# PR9016.net
KiCad netlist of a schematic drawn in EAGLE
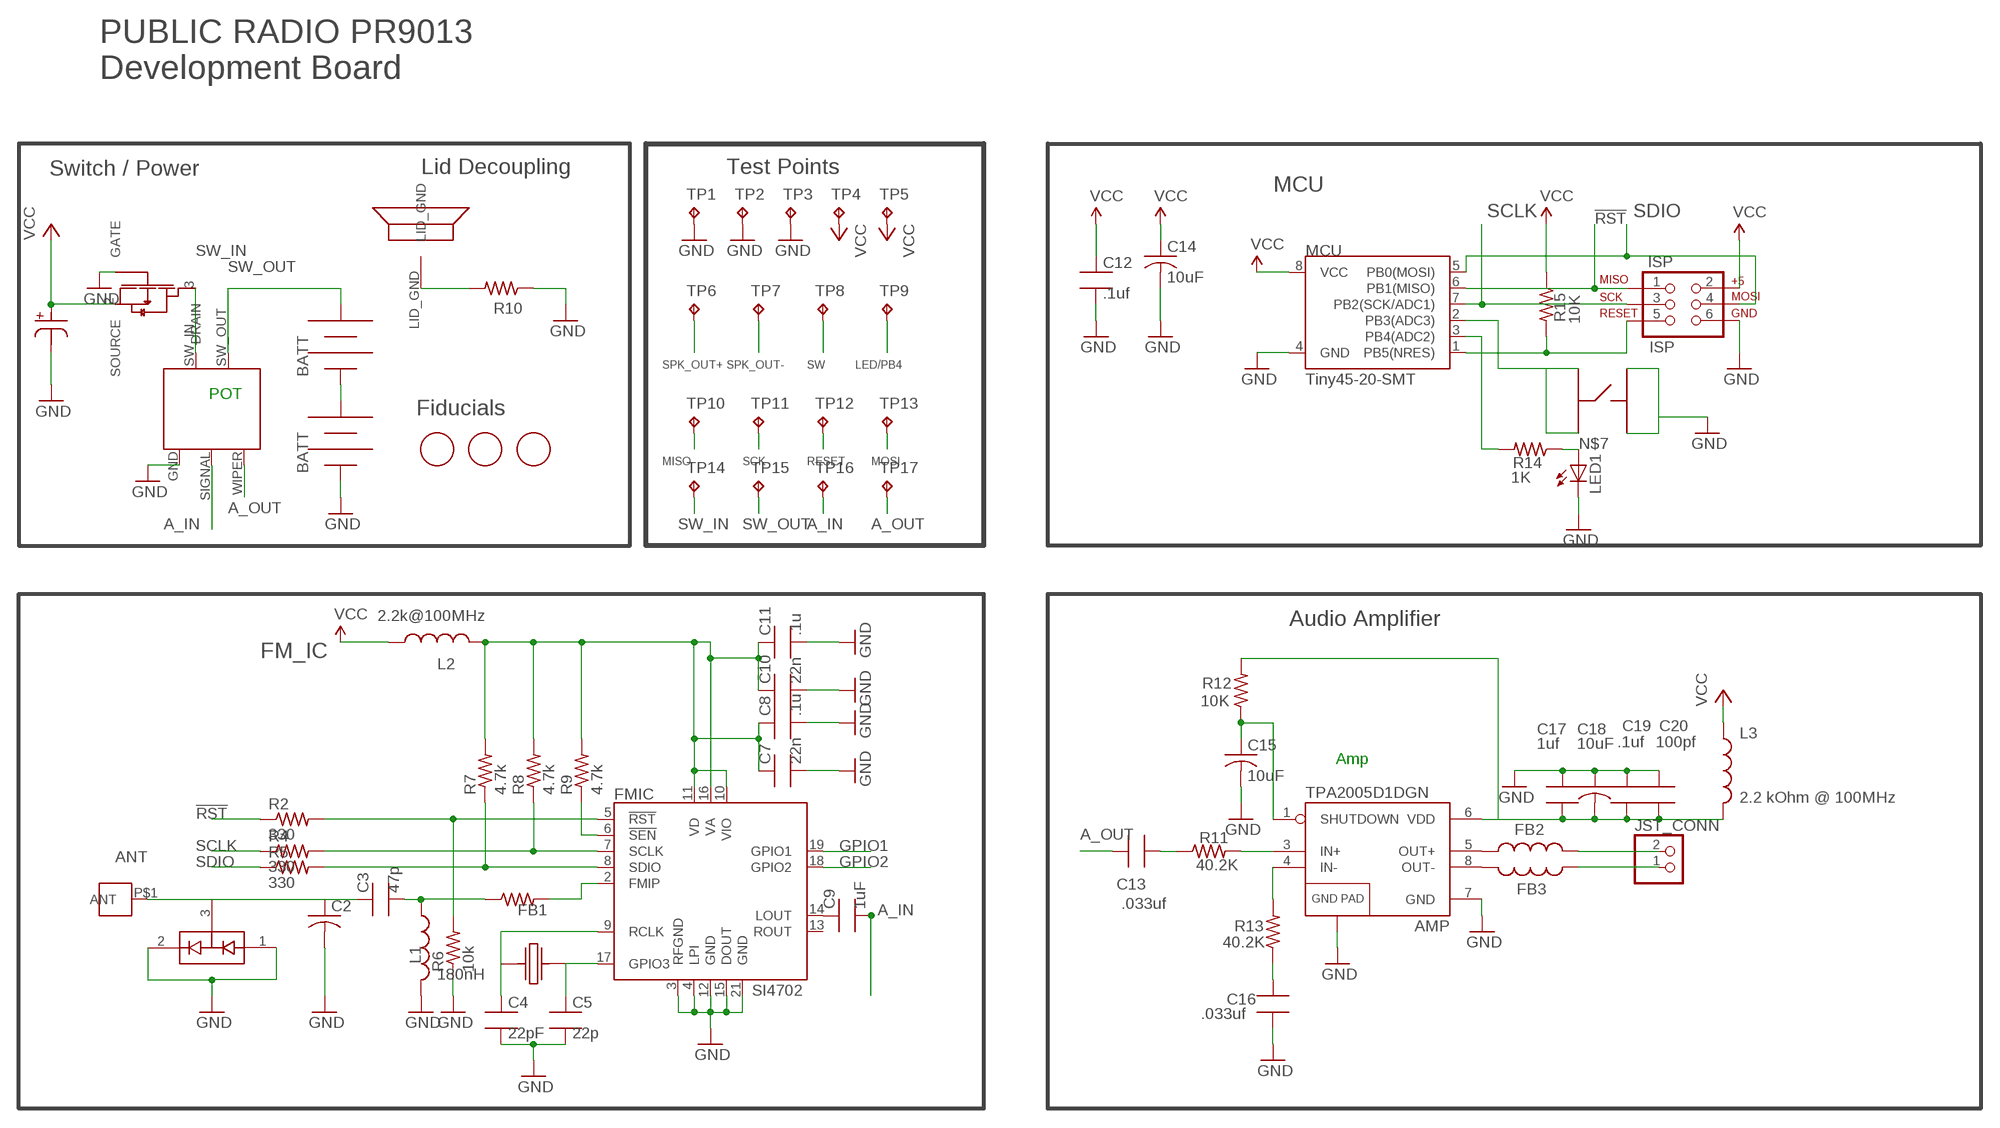
[diagram p0: schematic, sheet 1]

(export (version "E")
  (design (tool "Eeschema 10.0.6"))
  (components
    (comp (ref "AMP")
      (value "TPA2005D1DGN")
      (footprint "eagle-import:POWER-SOP8")
      (libsource (lib "eagle-import") (part "TPA2005D1DGN"))
    )
    (comp (ref "ANT_MOUNT")
      (value "M3_SCREW_POST")
      (footprint "eagle-import:M3_SCREW_POST")
      (libsource (lib "eagle-import") (part "M3_SCREW_POST"))
    )
    (comp (ref "C1")
      (value "220uF")
      (footprint "eagle-import:NICHICON_SERIESUD")
      (libsource (lib "eagle-import") (part "NICHICON_SERIESUD"))
    )
    (comp (ref "C2")
      (value "C-USC0805")
      (footprint "eagle-import:C0805")
      (libsource (lib "eagle-import") (part "C-USC0805"))
    )
    (comp (ref "C3")
      (value "47p")
      (footprint "eagle-import:C0402_WORTHINGTON")
      (libsource (lib "eagle-import") (part "CAP_SMT"))
    )
    (comp (ref "C4")
      (value "22pF")
      (footprint "eagle-import:C0402_WORTHINGTON")
      (libsource (lib "eagle-import") (part "CAP_SMT"))
    )
    (comp (ref "C5")
      (value "22p")
      (footprint "eagle-import:C0402_WORTHINGTON")
      (libsource (lib "eagle-import") (part "CAP_SMT"))
    )
    (comp (ref "C7")
      (value "22n")
      (footprint "eagle-import:C0402_WORTHINGTON")
      (libsource (lib "eagle-import") (part "CAP_SMT"))
    )
    (comp (ref "C8")
      (value ".1u")
      (footprint "eagle-import:C0402_WORTHINGTON")
      (libsource (lib "eagle-import") (part "CAP_SMT"))
    )
    (comp (ref "C9")
      (value "1uF")
      (footprint "eagle-import:C0402_WORTHINGTON")
      (libsource (lib "eagle-import") (part "CAP_SMT"))
    )
    (comp (ref "C10")
      (value "22n")
      (footprint "eagle-import:C0402_WORTHINGTON")
      (libsource (lib "eagle-import") (part "CAP_SMT"))
    )
    (comp (ref "C11")
      (value ".1u")
      (footprint "eagle-import:C0402_WORTHINGTON")
      (libsource (lib "eagle-import") (part "CAP_SMT"))
    )
    (comp (ref "C12")
      (value ".1uf")
      (footprint "eagle-import:C0402_WORTHINGTON")
      (libsource (lib "eagle-import") (part "CAP_SMT"))
    )
    (comp (ref "C13")
      (value ".033uf")
      (footprint "eagle-import:C0402_WORTHINGTON")
      (libsource (lib "eagle-import") (part "CAP_SMT"))
    )
    (comp (ref "C14")
      (value "10uF")
      (footprint "eagle-import:C0603")
      (libsource (lib "eagle-import") (part "C-USC0603"))
    )
    (comp (ref "C15")
      (value "10uF")
      (footprint "eagle-import:C0603")
      (libsource (lib "eagle-import") (part "C-USC0603"))
    )
    (comp (ref "C16")
      (value ".033uf")
      (footprint "eagle-import:C0402_WORTHINGTON")
      (libsource (lib "eagle-import") (part "CAP_SMT"))
    )
    (comp (ref "C17")
      (value "1uf")
      (footprint "eagle-import:C0402_WORTHINGTON")
      (libsource (lib "eagle-import") (part "CAP_SMT"))
    )
    (comp (ref "C18")
      (value "10uF")
      (footprint "eagle-import:C0603")
      (libsource (lib "eagle-import") (part "C-USC0603"))
    )
    (comp (ref "C19")
      (value ".1uf")
      (footprint "eagle-import:C0402_WORTHINGTON")
      (libsource (lib "eagle-import") (part "CAP_SMT"))
    )
    (comp (ref "C20")
      (value "100pf")
      (footprint "eagle-import:C0402_WORTHINGTON")
      (libsource (lib "eagle-import") (part "CAP_SMT"))
    )
    (comp (ref "D1")
      (value "BAV99")
      (footprint "eagle-import:SOT23")
      (libsource (lib "eagle-import") (part "BAV99"))
    )
    (comp (ref "FB1")
      (value "R-US_R0402")
      (footprint "eagle-import:R0402")
      (libsource (lib "eagle-import") (part "R-US_R0402"))
    )
    (comp (ref "FB2")
      (value "INDUCTOR0805")
      (footprint "eagle-import:0805")
      (libsource (lib "eagle-import") (part "INDUCTOR0805"))
    )
    (comp (ref "FB3")
      (value "INDUCTOR0805")
      (footprint "eagle-import:0805")
      (libsource (lib "eagle-import") (part "INDUCTOR0805"))
    )
    (comp (ref "FET1")
      (value "AO3435")
      (footprint "eagle-import:AO3435")
      (libsource (lib "eagle-import") (part "AO3435"))
    )
    (comp (ref "FMIC")
      (value "SI4702")
      (footprint "eagle-import:SI470X")
      (libsource (lib "eagle-import") (part "SI470X"))
    )
    (comp (ref "ISP")
      (value "ISP")
      (footprint "eagle-import:2X3-NS")
      (libsource (lib "eagle-import") (part "AVR_SPI_PRG_6NS"))
    )
    (comp (ref "JP5")
      (value "BK-92_MPD_AA_BATT_CLIP")
      (footprint "eagle-import:BK-92_MPD_AA_BATT_CLIP")
      (libsource (lib "eagle-import") (part "BK-92_MPD_AA_BATT_CLIP"))
    )
    (comp (ref "JP6")
      (value "BK-92_MPD_AA_BATT_CLIP")
      (footprint "eagle-import:BK-92_MPD_AA_BATT_CLIP")
      (libsource (lib "eagle-import") (part "BK-92_MPD_AA_BATT_CLIP"))
    )
    (comp (ref "JST_CONN")
      (value "JST_2PIN-SMT-RA")
      (footprint "eagle-import:JST-PH-2-SMT-RA")
      (libsource (lib "eagle-import") (part "JST_2PIN-SMT-RA"))
    )
    (comp (ref "L1")
      (value "180nH")
      (footprint "eagle-import:0805")
      (libsource (lib "eagle-import") (part "INDUCTOR0805"))
    )
    (comp (ref "L2")
      (value "2.2k@100MHz")
      (footprint "eagle-import:C0402_WORTHINGTON")
      (libsource (lib "eagle-import") (part "INDUCTOR"))
    )
    (comp (ref "L3")
      (value "2.2 kOhm @ 100MHz")
      (footprint "eagle-import:C0402_WORTHINGTON")
      (libsource (lib "eagle-import") (part "INDUCTOR"))
    )
    (comp (ref "LED1")
      (value "LEDSML0603")
      (footprint "eagle-import:SML0603")
      (libsource (lib "eagle-import") (part "LEDSML0603"))
    )
    (comp (ref "MARK1")
      (value "FIDUCIAL")
      (footprint "eagle-import:FIDUCIAL_1MM")
      (libsource (lib "eagle-import") (part "FIDUCIAL"))
    )
    (comp (ref "MARK2")
      (value "FIDUCIAL")
      (footprint "eagle-import:FIDUCIAL_1MM")
      (libsource (lib "eagle-import") (part "FIDUCIAL"))
    )
    (comp (ref "MARK3")
      (value "FIDUCIAL")
      (footprint "eagle-import:FIDUCIAL_1MM")
      (libsource (lib "eagle-import") (part "FIDUCIAL"))
    )
    (comp (ref "MCU")
      (value "Tiny45-20-SMT")
      (footprint "eagle-import:SO08-EIAJ")
      (libsource (lib "eagle-import") (part "ATTINY45TINY85-20-SMT"))
    )
    (comp (ref "R1")
      (value "RV170SF_TAIWANA_POT_SW")
      (footprint "eagle-import:RV170SF_TAIWANA_POT_SW")
      (libsource (lib "eagle-import") (part "RV170SF_TAIWANA_POT_SW"))
    )
    (comp (ref "R2")
      (value "330")
      (footprint "eagle-import:C0402_WORTHINGTON")
      (libsource (lib "eagle-import") (part "RES_SMT"))
    )
    (comp (ref "R4")
      (value "330")
      (footprint "eagle-import:C0402_WORTHINGTON")
      (libsource (lib "eagle-import") (part "RES_SMT"))
    )
    (comp (ref "R5")
      (value "330")
      (footprint "eagle-import:C0402_WORTHINGTON")
      (libsource (lib "eagle-import") (part "RES_SMT"))
    )
    (comp (ref "R6")
      (value "10k")
      (footprint "eagle-import:R0402")
      (libsource (lib "eagle-import") (part "R-US_R0402"))
    )
    (comp (ref "R7")
      (value "4.7k")
      (footprint "eagle-import:C0402_WORTHINGTON")
      (libsource (lib "eagle-import") (part "RES_SMT"))
    )
    (comp (ref "R8")
      (value "4.7k")
      (footprint "eagle-import:C0402_WORTHINGTON")
      (libsource (lib "eagle-import") (part "RES_SMT"))
    )
    (comp (ref "R9")
      (value "4.7k")
      (footprint "eagle-import:C0402_WORTHINGTON")
      (libsource (lib "eagle-import") (part "RES_SMT"))
    )
    (comp (ref "R10")
      (value "R-US_R0805")
      (footprint "eagle-import:R0805")
      (libsource (lib "eagle-import") (part "R-US_R0805"))
    )
    (comp (ref "R11")
      (value "40.2K")
      (footprint "eagle-import:C0402_WORTHINGTON")
      (libsource (lib "eagle-import") (part "RES_SMT"))
    )
    (comp (ref "R12")
      (value "10K")
      (footprint "eagle-import:C0402_WORTHINGTON")
      (libsource (lib "eagle-import") (part "RES_SMT"))
    )
    (comp (ref "R13")
      (value "40.2K")
      (footprint "eagle-import:C0402_WORTHINGTON")
      (libsource (lib "eagle-import") (part "RES_SMT"))
    )
    (comp (ref "R14")
      (value "1K")
      (footprint "eagle-import:C0402_WORTHINGTON")
      (libsource (lib "eagle-import") (part "RES_SMT"))
    )
    (comp (ref "R15")
      (value "10K")
      (footprint "eagle-import:C0402_WORTHINGTON")
      (libsource (lib "eagle-import") (part "RES_SMT"))
    )
    (comp (ref "SPKR_PLACE")
      (value "CE32A_FOR_JST")
      (footprint "eagle-import:CE32A_FOR_JST")
      (libsource (lib "eagle-import") (part "PR_Parts_Library_CE32A_FOR_JST"))
    )
    (comp (ref "SW1")
      (value "C&K_PTS645")
      (footprint "eagle-import:C&K_TACTILE_SWITCH")
      (libsource (lib "eagle-import") (part "C&K_PTS645"))
    )
    (comp (ref "TP1")
      (value "TPTP20R")
      (footprint "eagle-import:TP20R")
      (libsource (lib "eagle-import") (part "TPTP20R"))
    )
    (comp (ref "TP2")
      (value "TPTP20R")
      (footprint "eagle-import:TP20R")
      (libsource (lib "eagle-import") (part "TPTP20R"))
    )
    (comp (ref "TP3")
      (value "TPTP20R")
      (footprint "eagle-import:TP20R")
      (libsource (lib "eagle-import") (part "TPTP20R"))
    )
    (comp (ref "TP4")
      (value "TPTP20R")
      (footprint "eagle-import:TP20R")
      (libsource (lib "eagle-import") (part "TPTP20R"))
    )
    (comp (ref "TP5")
      (value "TPTP20R")
      (footprint "eagle-import:TP20R")
      (libsource (lib "eagle-import") (part "TPTP20R"))
    )
    (comp (ref "TP6")
      (value "TPTP20R")
      (footprint "eagle-import:TP20R")
      (libsource (lib "eagle-import") (part "TPTP20R"))
    )
    (comp (ref "TP7")
      (value "TPTP20R")
      (footprint "eagle-import:TP20R")
      (libsource (lib "eagle-import") (part "TPTP20R"))
    )
    (comp (ref "TP8")
      (value "TPTP20R")
      (footprint "eagle-import:TP20R")
      (libsource (lib "eagle-import") (part "TPTP20R"))
    )
    (comp (ref "TP9")
      (value "TPTP20R")
      (footprint "eagle-import:TP20R")
      (libsource (lib "eagle-import") (part "TPTP20R"))
    )
    (comp (ref "TP10")
      (value "TPTP20R")
      (footprint "eagle-import:TP20R")
      (libsource (lib "eagle-import") (part "TPTP20R"))
    )
    (comp (ref "TP11")
      (value "TPTP20R")
      (footprint "eagle-import:TP20R")
      (libsource (lib "eagle-import") (part "TPTP20R"))
    )
    (comp (ref "TP12")
      (value "TPTP20R")
      (footprint "eagle-import:TP20R")
      (libsource (lib "eagle-import") (part "TPTP20R"))
    )
    (comp (ref "TP13")
      (value "TPTP20R")
      (footprint "eagle-import:TP20R")
      (libsource (lib "eagle-import") (part "TPTP20R"))
    )
    (comp (ref "TP14")
      (value "TPTP20R")
      (footprint "eagle-import:TP20R")
      (libsource (lib "eagle-import") (part "TPTP20R"))
    )
    (comp (ref "TP15")
      (value "TPTP20R")
      (footprint "eagle-import:TP20R")
      (libsource (lib "eagle-import") (part "TPTP20R"))
    )
    (comp (ref "TP16")
      (value "TPTP20R")
      (footprint "eagle-import:TP20R")
      (libsource (lib "eagle-import") (part "TPTP20R"))
    )
    (comp (ref "TP17")
      (value "TPTP20R")
      (footprint "eagle-import:TP20R")
      (libsource (lib "eagle-import") (part "TPTP20R"))
    )
    (comp (ref "Y1")
      (value "ABS25XTAL")
      (footprint "eagle-import:ABS25XTAL")
      (libsource (lib "eagle-import") (part "ABS25XTAL"))
    )
  )
  (nets
    (net (code "1") (name "/ANT") (class "Default")
      (node (ref "ANT_MOUNT") (pin "P$1") (pinfunction "ANT_P$1") (pintype "bidirectional"))
      (node (ref "C2") (pin "1") (pinfunction "1_1") (pintype "passive"))
      (node (ref "C3") (pin "1") (pinfunction "1_1") (pintype "passive"))
      (node (ref "D1") (pin "3") (pinfunction "COM_3") (pintype "bidirectional"))
    )
    (net (code "2") (name "/A_IN") (class "Default")
      (node (ref "C9") (pin "2") (pinfunction "2_2") (pintype "passive"))
      (node (ref "R1") (pin "SIGNAL") (pinfunction "SIGNAL_SIGNAL") (pintype "bidirectional"))
      (node (ref "TP16") (pin "TP") (pinfunction "TP_TP") (pintype "input"))
    )
    (net (code "3") (name "/A_OUT") (class "Default")
      (node (ref "C13") (pin "1") (pinfunction "1_1") (pintype "passive"))
      (node (ref "R1") (pin "WIPER") (pinfunction "WIPER_WIPER") (pintype "bidirectional"))
      (node (ref "TP17") (pin "TP") (pinfunction "TP_TP") (pintype "input"))
    )
    (net (code "4") (name "/GPIO1") (class "Default")
      (node (ref "FMIC") (pin "19") (pinfunction "GPIO1_19") (pintype "bidirectional"))
    )
    (net (code "5") (name "/GPIO2") (class "Default")
      (node (ref "FMIC") (pin "18") (pinfunction "GPIO2_18") (pintype "bidirectional"))
    )
    (net (code "6") (name "/LED{slash}PB4") (class "Default")
      (node (ref "MCU") (pin "3") (pinfunction "PB4(ADC2)_3") (pintype "bidirectional"))
      (node (ref "R14") (pin "2") (pinfunction "2_2") (pintype "passive"))
      (node (ref "TP9") (pin "TP") (pinfunction "TP_TP") (pintype "input"))
    )
    (net (code "7") (name "/N$7") (class "Default")
      (node (ref "LED1") (pin "A") (pinfunction "A_A") (pintype "passive"))
      (node (ref "R14") (pin "1") (pinfunction "1_1") (pintype "passive"))
    )
    (net (code "8") (name "/RESET") (class "Default")
      (node (ref "ISP") (pin "5") (pinfunction "5_5") (pintype "passive"))
      (node (ref "MCU") (pin "1") (pinfunction "PB5(NRES)_1") (pintype "bidirectional"))
      (node (ref "R15") (pin "2") (pinfunction "2_2") (pintype "passive"))
      (node (ref "TP12") (pin "TP") (pinfunction "TP_TP") (pintype "input"))
    )
    (net (code "9") (name "/SCLK") (class "Default")
      (node (ref "ISP") (pin "3") (pinfunction "3_3") (pintype "passive"))
      (node (ref "MCU") (pin "7") (pinfunction "PB2(SCK/ADC1)_7") (pintype "bidirectional"))
      (node (ref "R4") (pin "1") (pinfunction "1_1") (pintype "passive"))
      (node (ref "TP11") (pin "TP") (pinfunction "TP_TP") (pintype "input"))
    )
    (net (code "10") (name "/SDIO") (class "Default")
      (node (ref "ISP") (pin "4") (pinfunction "4_4") (pintype "passive"))
      (node (ref "MCU") (pin "5") (pinfunction "PB0(MOSI)_5") (pintype "bidirectional"))
      (node (ref "R5") (pin "1") (pinfunction "1_1") (pintype "passive"))
      (node (ref "TP13") (pin "TP") (pinfunction "TP_TP") (pintype "input"))
    )
    (net (code "11") (name "/SPK_OUT+") (class "Default")
      (node (ref "FB2") (pin "2") (pinfunction "2_2") (pintype "passive"))
      (node (ref "JST_CONN") (pin "2") (pinfunction "1_2") (pintype "passive"))
      (node (ref "TP6") (pin "TP") (pinfunction "TP_TP") (pintype "input"))
    )
    (net (code "12") (name "/SPK_OUT-") (class "Default")
      (node (ref "FB3") (pin "1") (pinfunction "1_1") (pintype "passive"))
      (node (ref "JST_CONN") (pin "1") (pinfunction "2_1") (pintype "passive"))
      (node (ref "TP7") (pin "TP") (pinfunction "TP_TP") (pintype "input"))
    )
    (net (code "13") (name "/SW") (class "Default")
      (node (ref "MCU") (pin "2") (pinfunction "PB3(ADC3)_2") (pintype "bidirectional"))
      (node (ref "SW1") (pin "P$3") (pinfunction "P$3_P$3") (pintype "bidirectional"))
      (node (ref "SW1") (pin "P$4") (pinfunction "P$4_P$4") (pintype "bidirectional"))
      (node (ref "TP8") (pin "TP") (pinfunction "TP_TP") (pintype "input"))
    )
    (net (code "14") (name "/SW_IN") (class "Default")
      (node (ref "FET1") (pin "3") (pinfunction "DRAIN_3") (pintype "bidirectional"))
      (node (ref "R1") (pin "SW_IN") (pinfunction "SW_IN_SW_IN") (pintype "bidirectional"))
      (node (ref "TP14") (pin "TP") (pinfunction "TP_TP") (pintype "input"))
    )
    (net (code "15") (name "/SW_OUT") (class "Default")
      (node (ref "JP5") (pin "POS") (pinfunction "POS_POS") (pintype "bidirectional"))
      (node (ref "JP5") (pin "POS@2") (pinfunction "POS_POS@2") (pintype "bidirectional"))
      (node (ref "R1") (pin "SW_OUT") (pinfunction "SW_OUT_SW_OUT") (pintype "bidirectional"))
      (node (ref "TP15") (pin "TP") (pinfunction "TP_TP") (pintype "input"))
    )
    (net (code "16") (name "/~{RST}") (class "Default")
      (node (ref "ISP") (pin "1") (pinfunction "1_1") (pintype "passive"))
      (node (ref "MCU") (pin "6") (pinfunction "PB1(MISO)_6") (pintype "bidirectional"))
      (node (ref "R2") (pin "1") (pinfunction "1_1") (pintype "passive"))
      (node (ref "TP10") (pin "TP") (pinfunction "TP_TP") (pintype "input"))
    )
    (net (code "17") (name "GND") (class "Default")
      (node (ref "AMP") (pin "7") (pinfunction "GND_7") (pintype "power_in"))
      (node (ref "AMP") (pin "9") (pinfunction "GND_9") (pintype "power_in"))
      (node (ref "C1") (pin "P$2") (pinfunction "P$2_P$2") (pintype "bidirectional"))
      (node (ref "C10") (pin "2") (pinfunction "2_2") (pintype "passive"))
      (node (ref "C11") (pin "2") (pinfunction "2_2") (pintype "passive"))
      (node (ref "C12") (pin "2") (pinfunction "2_2") (pintype "passive"))
      (node (ref "C14") (pin "2") (pinfunction "2_2") (pintype "passive"))
      (node (ref "C15") (pin "2") (pinfunction "2_2") (pintype "passive"))
      (node (ref "C16") (pin "1") (pinfunction "1_1") (pintype "passive"))
      (node (ref "C17") (pin "1") (pinfunction "1_1") (pintype "passive"))
      (node (ref "C18") (pin "1") (pinfunction "1_1") (pintype "passive"))
      (node (ref "C19") (pin "1") (pinfunction "1_1") (pintype "passive"))
      (node (ref "C2") (pin "2") (pinfunction "2_2") (pintype "passive"))
      (node (ref "C20") (pin "1") (pinfunction "1_1") (pintype "passive"))
      (node (ref "C4") (pin "2") (pinfunction "2_2") (pintype "passive"))
      (node (ref "C5") (pin "2") (pinfunction "2_2") (pintype "passive"))
      (node (ref "C7") (pin "2") (pinfunction "2_2") (pintype "passive"))
      (node (ref "C8") (pin "2") (pinfunction "2_2") (pintype "passive"))
      (node (ref "D1") (pin "1") (pinfunction "A1_1") (pintype "bidirectional"))
      (node (ref "D1") (pin "2") (pinfunction "C2_2") (pintype "bidirectional"))
      (node (ref "FET1") (pin "1") (pinfunction "GATE_1") (pintype "bidirectional"))
      (node (ref "FMIC") (pin "12") (pinfunction "GND_12") (pintype "bidirectional"))
      (node (ref "FMIC") (pin "15") (pinfunction "DOUT_15") (pintype "bidirectional"))
      (node (ref "FMIC") (pin "21") (pinfunction "GND_21") (pintype "bidirectional"))
      (node (ref "FMIC") (pin "3") (pinfunction "RFGND_3") (pintype "bidirectional"))
      (node (ref "FMIC") (pin "4") (pinfunction "LPI_4") (pintype "bidirectional"))
      (node (ref "ISP") (pin "6") (pinfunction "6_6") (pintype "passive"))
      (node (ref "JP6") (pin "NEG") (pinfunction "NEG_NEG") (pintype "bidirectional"))
      (node (ref "JP6") (pin "NEG@2") (pinfunction "NEG_NEG@2") (pintype "bidirectional"))
      (node (ref "L1") (pin "2") (pinfunction "2_2") (pintype "passive"))
      (node (ref "LED1") (pin "C") (pinfunction "C_C") (pintype "passive"))
      (node (ref "MCU") (pin "4") (pinfunction "GND_4") (pintype "bidirectional"))
      (node (ref "R1") (pin "GND") (pinfunction "GND_GND") (pintype "bidirectional"))
      (node (ref "R10") (pin "1") (pinfunction "1_1") (pintype "passive"))
      (node (ref "R6") (pin "1") (pinfunction "1_1") (pintype "passive"))
      (node (ref "SW1") (pin "P$1") (pinfunction "P$1_P$1") (pintype "bidirectional"))
      (node (ref "SW1") (pin "P$2") (pinfunction "P$2_P$2") (pintype "bidirectional"))
      (node (ref "TP1") (pin "TP") (pinfunction "TP_TP") (pintype "input"))
      (node (ref "TP2") (pin "TP") (pinfunction "TP_TP") (pintype "input"))
      (node (ref "TP3") (pin "TP") (pinfunction "TP_TP") (pintype "input"))
    )
    (net (code "18") (name "Net-(AMP-IN+)") (class "Default")
      (node (ref "AMP") (pin "3") (pinfunction "IN+_3") (pintype "bidirectional"))
      (node (ref "R11") (pin "2") (pinfunction "2_2") (pintype "passive"))
    )
    (net (code "19") (name "Net-(AMP-IN-)") (class "Default")
      (node (ref "AMP") (pin "4") (pinfunction "IN-_4") (pintype "bidirectional"))
      (node (ref "R13") (pin "2") (pinfunction "2_2") (pintype "passive"))
    )
    (net (code "20") (name "Net-(AMP-OUT+)") (class "Default")
      (node (ref "AMP") (pin "5") (pinfunction "OUT+_5") (pintype "bidirectional"))
      (node (ref "FB2") (pin "1") (pinfunction "1_1") (pintype "passive"))
    )
    (net (code "21") (name "Net-(AMP-OUT-)") (class "Default")
      (node (ref "AMP") (pin "8") (pinfunction "OUT-_8") (pintype "bidirectional"))
      (node (ref "FB3") (pin "2") (pinfunction "2_2") (pintype "passive"))
    )
    (net (code "22") (name "Net-(AMP-SHUTDOWN)") (class "Default")
      (node (ref "AMP") (pin "1") (pinfunction "SHUTDOWN_1") (pintype "input"))
      (node (ref "C15") (pin "1") (pinfunction "1_1") (pintype "passive"))
      (node (ref "R12") (pin "1") (pinfunction "1_1") (pintype "passive"))
    )
    (net (code "23") (name "Net-(AMP-VDD)") (class "Default")
      (node (ref "AMP") (pin "6") (pinfunction "VDD_6") (pintype "power_in"))
      (node (ref "C17") (pin "2") (pinfunction "2_2") (pintype "passive"))
      (node (ref "C18") (pin "2") (pinfunction "2_2") (pintype "passive"))
      (node (ref "C19") (pin "2") (pinfunction "2_2") (pintype "passive"))
      (node (ref "C20") (pin "2") (pinfunction "2_2") (pintype "passive"))
      (node (ref "L3") (pin "2") (pinfunction "2_2") (pintype "passive"))
      (node (ref "R12") (pin "2") (pinfunction "2_2") (pintype "passive"))
    )
    (net (code "24") (name "Net-(C3-Pad2)") (class "Default")
      (node (ref "C3") (pin "2") (pinfunction "2_2") (pintype "passive"))
      (node (ref "FB1") (pin "1") (pinfunction "1_1") (pintype "passive"))
      (node (ref "L1") (pin "1") (pinfunction "1_1") (pintype "passive"))
    )
    (net (code "25") (name "Net-(C13-Pad2)") (class "Default")
      (node (ref "C13") (pin "2") (pinfunction "2_2") (pintype "passive"))
      (node (ref "R11") (pin "1") (pinfunction "1_1") (pintype "passive"))
    )
    (net (code "26") (name "Net-(C16-Pad2)") (class "Default")
      (node (ref "C16") (pin "2") (pinfunction "2_2") (pintype "passive"))
      (node (ref "R13") (pin "1") (pinfunction "1_1") (pintype "passive"))
    )
    (net (code "27") (name "Net-(FMIC-FMIP)") (class "Default")
      (node (ref "FB1") (pin "2") (pinfunction "2_2") (pintype "passive"))
      (node (ref "FMIC") (pin "2") (pinfunction "FMIP_2") (pintype "bidirectional"))
    )
    (net (code "28") (name "Net-(FMIC-GPIO3)") (class "Default")
      (node (ref "C5") (pin "1") (pinfunction "1_1") (pintype "passive"))
      (node (ref "FMIC") (pin "17") (pinfunction "GPIO3_17") (pintype "bidirectional"))
      (node (ref "Y1") (pin "P$4") (pinfunction "P$4_P$4") (pintype "bidirectional"))
    )
    (net (code "29") (name "Net-(FMIC-LOUT)") (class "Default")
      (node (ref "C9") (pin "1") (pinfunction "1_1") (pintype "passive"))
      (node (ref "FMIC") (pin "14") (pinfunction "LOUT_14") (pintype "bidirectional"))
    )
    (net (code "30") (name "Net-(FMIC-RCLK)") (class "Default")
      (node (ref "C4") (pin "1") (pinfunction "1_1") (pintype "passive"))
      (node (ref "FMIC") (pin "9") (pinfunction "RCLK_9") (pintype "bidirectional"))
      (node (ref "Y1") (pin "P$1") (pinfunction "P$1_P$1") (pintype "bidirectional"))
    )
    (net (code "31") (name "Net-(FMIC-SCLK)") (class "Default")
      (node (ref "FMIC") (pin "7") (pinfunction "SCLK_7") (pintype "bidirectional"))
      (node (ref "R4") (pin "2") (pinfunction "2_2") (pintype "passive"))
      (node (ref "R8") (pin "1") (pinfunction "1_1") (pintype "passive"))
    )
    (net (code "32") (name "Net-(FMIC-SDIO)") (class "Default")
      (node (ref "FMIC") (pin "8") (pinfunction "SDIO_8") (pintype "bidirectional"))
      (node (ref "R5") (pin "2") (pinfunction "2_2") (pintype "passive"))
      (node (ref "R7") (pin "1") (pinfunction "1_1") (pintype "passive"))
    )
    (net (code "33") (name "Net-(FMIC-VA)") (class "Default")
      (node (ref "C10") (pin "1") (pinfunction "1_1") (pintype "passive"))
      (node (ref "C11") (pin "1") (pinfunction "1_1") (pintype "passive"))
      (node (ref "C7") (pin "1") (pinfunction "1_1") (pintype "passive"))
      (node (ref "C8") (pin "1") (pinfunction "1_1") (pintype "passive"))
      (node (ref "FMIC") (pin "10") (pinfunction "VIO_10") (pintype "bidirectional"))
      (node (ref "FMIC") (pin "11") (pinfunction "VD_11") (pintype "bidirectional"))
      (node (ref "FMIC") (pin "16") (pinfunction "VA_16") (pintype "bidirectional"))
      (node (ref "L2") (pin "2") (pinfunction "2_2") (pintype "passive"))
      (node (ref "R7") (pin "2") (pinfunction "2_2") (pintype "passive"))
      (node (ref "R8") (pin "2") (pinfunction "2_2") (pintype "passive"))
      (node (ref "R9") (pin "2") (pinfunction "2_2") (pintype "passive"))
    )
    (net (code "34") (name "Net-(FMIC-~{RST})") (class "Default")
      (node (ref "FMIC") (pin "5") (pinfunction "~{RST}_5") (pintype "bidirectional"))
      (node (ref "R2") (pin "2") (pinfunction "2_2") (pintype "passive"))
      (node (ref "R6") (pin "2") (pinfunction "2_2") (pintype "passive"))
    )
    (net (code "35") (name "Net-(FMIC-~{SEN})") (class "Default")
      (node (ref "FMIC") (pin "6") (pinfunction "~{SEN}_6") (pintype "bidirectional"))
      (node (ref "R9") (pin "1") (pinfunction "1_1") (pintype "passive"))
    )
    (net (code "36") (name "Net-(JP5-NEG-PadNEG@2)") (class "Default")
      (node (ref "JP5") (pin "NEG") (pinfunction "NEG_NEG") (pintype "bidirectional"))
      (node (ref "JP5") (pin "NEG@2") (pinfunction "NEG_NEG@2") (pintype "bidirectional"))
      (node (ref "JP6") (pin "POS") (pinfunction "POS_POS") (pintype "bidirectional"))
      (node (ref "JP6") (pin "POS@2") (pinfunction "POS_POS@2") (pintype "bidirectional"))
    )
    (net (code "37") (name "Net-(R10-Pad2)") (class "Default")
      (node (ref "R10") (pin "2") (pinfunction "2_2") (pintype "passive"))
      (node (ref "SPKR_PLACE") (pin "LID_GND") (pinfunction "LID_GND_LID_GND") (pintype "bidirectional"))
    )
    (net (code "38") (name "VCC") (class "Default")
      (node (ref "C1") (pin "P$1") (pinfunction "P$1_P$1") (pintype "bidirectional"))
      (node (ref "C12") (pin "1") (pinfunction "1_1") (pintype "passive"))
      (node (ref "C14") (pin "1") (pinfunction "1_1") (pintype "passive"))
      (node (ref "FET1") (pin "2") (pinfunction "SOURCE_2") (pintype "bidirectional"))
      (node (ref "ISP") (pin "2") (pinfunction "2_2") (pintype "passive"))
      (node (ref "L2") (pin "1") (pinfunction "1_1") (pintype "passive"))
      (node (ref "L3") (pin "1") (pinfunction "1_1") (pintype "passive"))
      (node (ref "MCU") (pin "8") (pinfunction "VCC_8") (pintype "bidirectional"))
      (node (ref "R15") (pin "1") (pinfunction "1_1") (pintype "passive"))
      (node (ref "TP4") (pin "TP") (pinfunction "TP_TP") (pintype "input"))
      (node (ref "TP5") (pin "TP") (pinfunction "TP_TP") (pintype "input"))
    )
    (net (code "39") (name "unconnected-(FMIC-ROUT-Pad13)") (class "Default")
      (node (ref "FMIC") (pin "13") (pinfunction "ROUT_13") (pintype "bidirectional"))
    )
  )
)
